# Test10122022.net
KiCad netlist of a schematic drawn in EAGLE
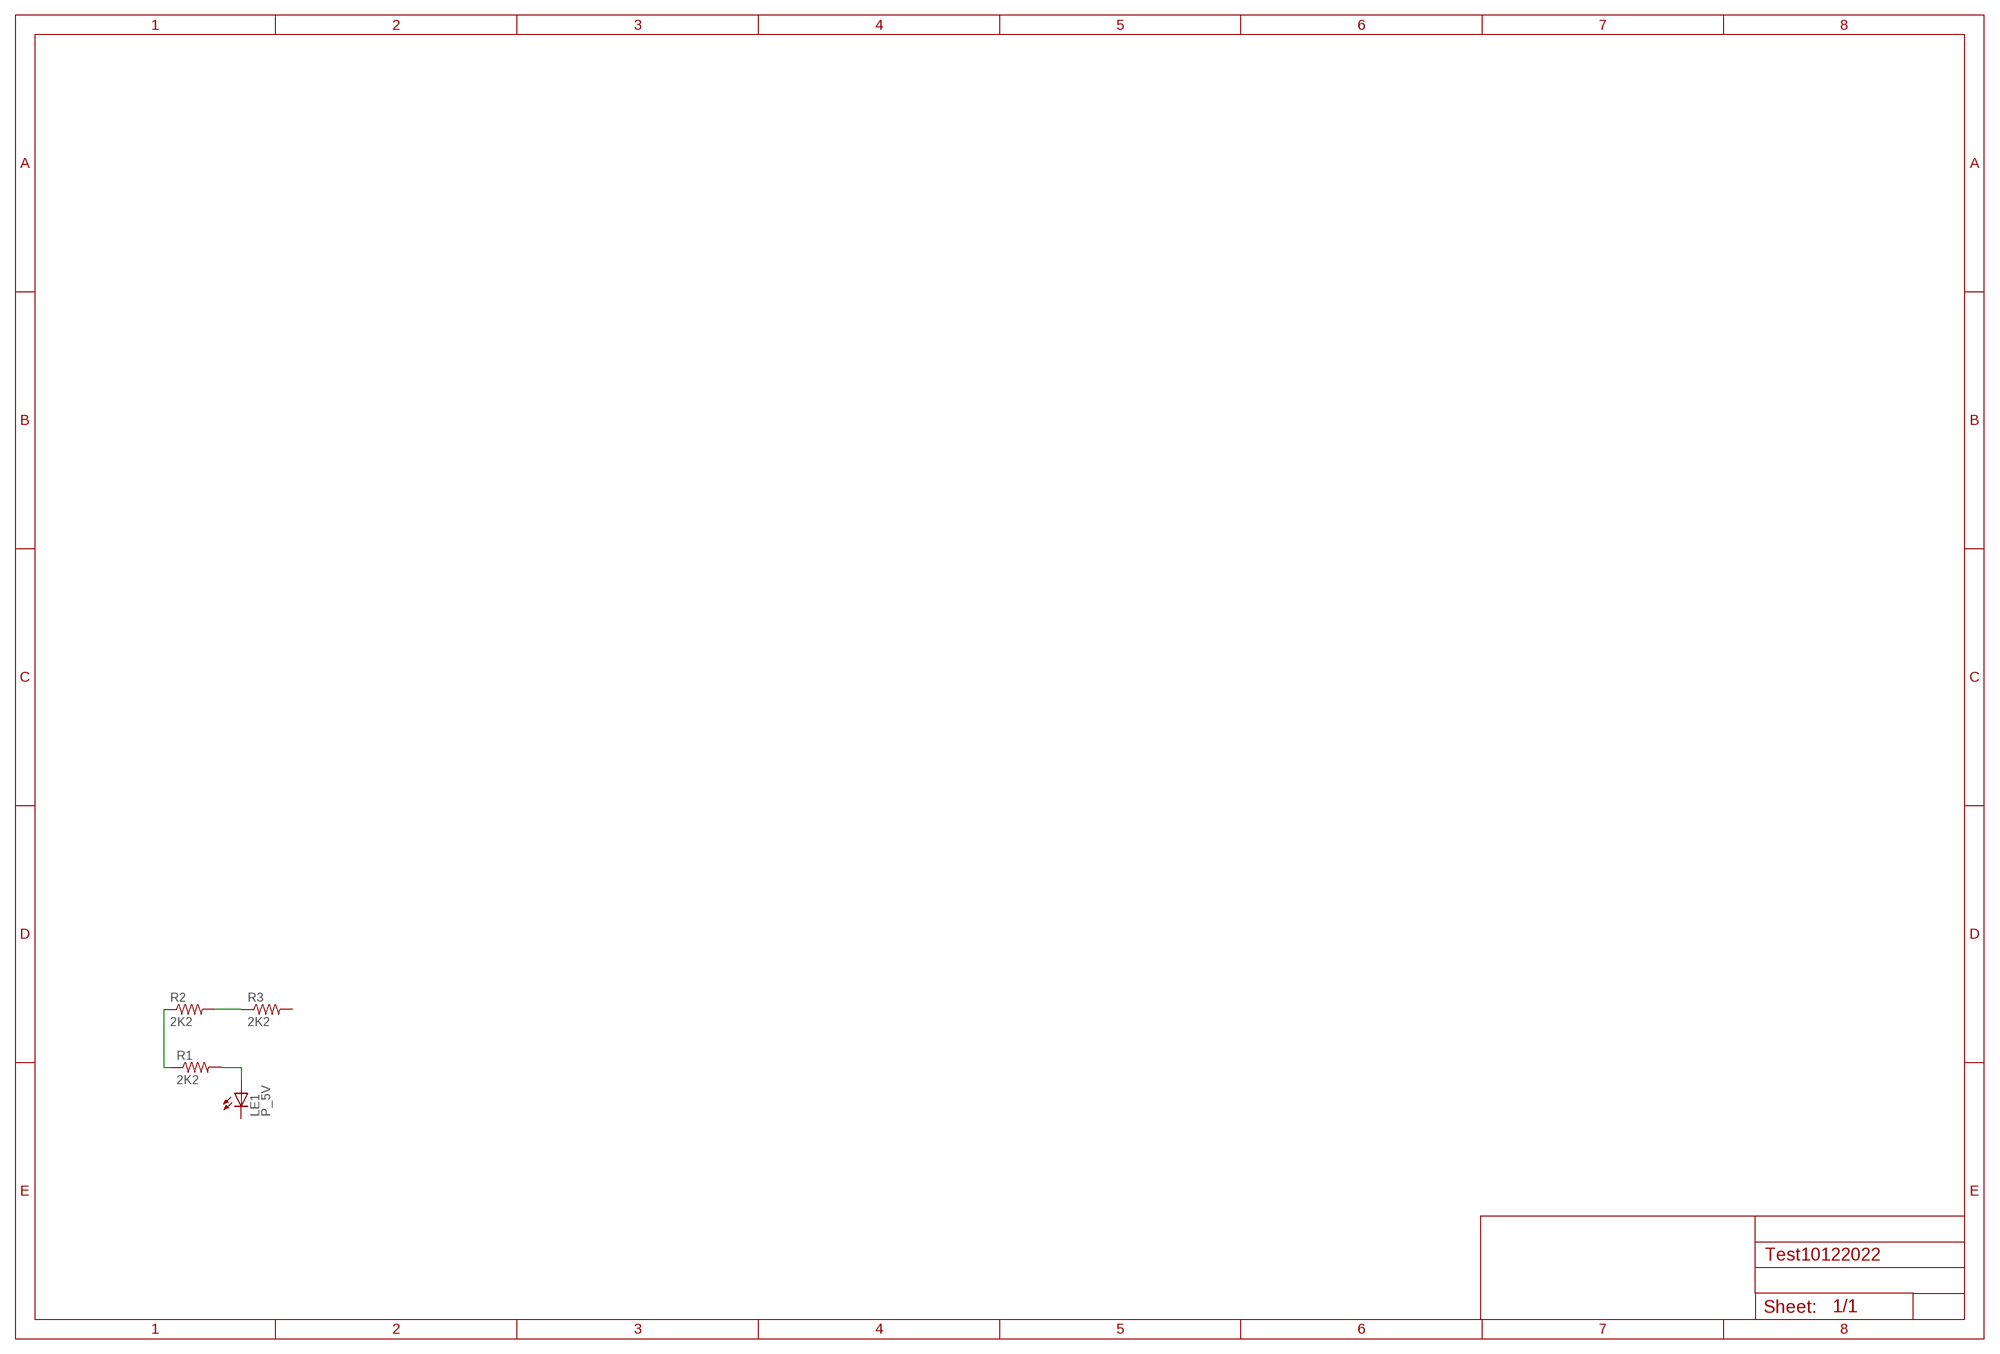
[diagram p0: schematic, sheet 1]

(export (version "E")
  (design (tool "Eeschema 10.0.6"))
  (components
    (comp (ref "LE1")
      (value "P_5V")
      (footprint "eagle-import:0603P")
      (libsource (lib "eagle-import") (part "LED0603"))
    )
    (comp (ref "R1")
      (value "2K2")
      (footprint "eagle-import:R0603")
      (libsource (lib "eagle-import") (part "R0603"))
    )
    (comp (ref "R2")
      (value "2K2")
      (footprint "eagle-import:R0603")
      (libsource (lib "eagle-import") (part "R0603"))
    )
    (comp (ref "R3")
      (value "2K2")
      (footprint "eagle-import:R0603")
      (libsource (lib "eagle-import") (part "R0603"))
    )
  )
  (nets
    (net (code "1") (name "Net-(LE1-A)") (class "Default")
      (node (ref "LE1") (pin "2") (pinfunction "A_2") (pintype "passive"))
      (node (ref "R1") (pin "2") (pinfunction "2_2") (pintype "passive"))
    )
    (net (code "2") (name "Net-(R1-Pad1)") (class "Default")
      (node (ref "R1") (pin "1") (pinfunction "1_1") (pintype "passive"))
      (node (ref "R2") (pin "1") (pinfunction "1_1") (pintype "passive"))
    )
    (net (code "3") (name "Net-(R2-Pad2)") (class "Default")
      (node (ref "R2") (pin "2") (pinfunction "2_2") (pintype "passive"))
      (node (ref "R3") (pin "1") (pinfunction "1_1") (pintype "passive"))
    )
    (net (code "4") (name "unconnected-(LE1-C-Pad1)") (class "Default")
      (node (ref "LE1") (pin "1") (pinfunction "C_1") (pintype "passive"))
    )
    (net (code "5") (name "unconnected-(R3-Pad2)") (class "Default")
      (node (ref "R3") (pin "2") (pinfunction "2_2") (pintype "passive"))
    )
  )
)
